# P_08__CPU_MISC.net
KiCad netlist of a schematic drawn in Altium Designer
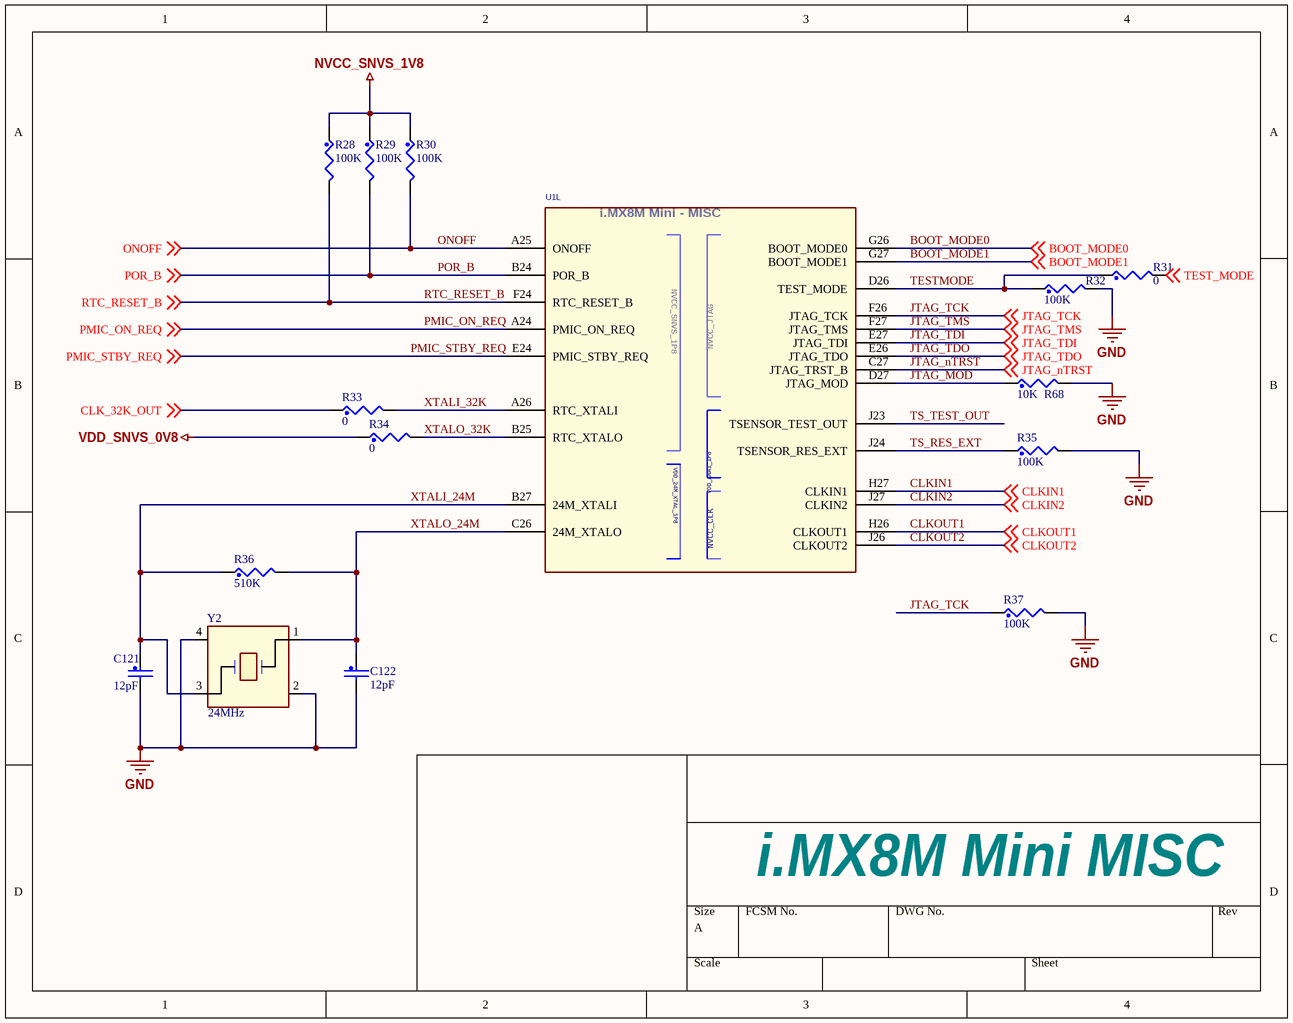
[diagram p0: P[08]_CPU_MISC.SchDoc]

(export (version "E")
  (design (tool "Eeschema 10.0.6"))
  (components
    (comp (ref "C121")
      (value "12pF")
      (footprint "0201_CC - C")
      (libsource (lib "AA_iMX8_M_") (part "CAP_NP"))
    )
    (comp (ref "C122")
      (value "12pF")
      (footprint "0201_CC - C")
      (libsource (lib "AA_iMX8_M_") (part "CAP_NP"))
    )
    (comp (ref "R28") (value "100K") (footprint "0201_CC") (libsource (lib "AA_iMX8_M_") (part "RES")))
    (comp (ref "R29") (value "100K") (footprint "0201_CC") (libsource (lib "AA_iMX8_M_") (part "RES")))
    (comp (ref "R30") (value "100K") (footprint "0201_CC") (libsource (lib "AA_iMX8_M_") (part "RES")))
    (comp (ref "R31") (value "0") (footprint "0402_CC") (libsource (lib "AA_iMX8_M_") (part "RES")))
    (comp (ref "R32") (value "100K") (footprint "0201_CC") (libsource (lib "AA_iMX8_M_") (part "RES")))
    (comp (ref "R33") (value "0") (footprint "0402_CC") (libsource (lib "AA_iMX8_M_") (part "RES")))
    (comp (ref "R34") (value "0") (footprint "0402_CC") (libsource (lib "AA_iMX8_M_") (part "RES")))
    (comp (ref "R35") (value "100K") (footprint "0201_CC") (libsource (lib "AA_iMX8_M_") (part "RES")))
    (comp (ref "R36") (value "510K") (footprint "0402_CC") (libsource (lib "AA_iMX8_M_") (part "RES")))
    (comp (ref "R37") (value "100K") (footprint "0201_CC") (libsource (lib "AA_iMX8_M_") (part "RES")))
    (comp (ref "R68") (value "10K") (footprint "0201_CC") (libsource (lib "AA_iMX8_M_") (part "RES")))
    (comp (ref "U1")
      (value "SFP_CGND")
      (footprint "BGA486_0P5_14X14")
      (description "IC CPU QUAD CORTEX A53+M4 1.8GHZ BGA486 / By Arman Arvand")
      (libsource (lib "AA_iMX8_M_") (part "MIMX8MM_BGA486P"))
    )
    (comp (ref "Y2")
      (value "24MHz")
      (footprint "OSCCC320X250X60")
      (libsource (lib "AA_iMX8_M_") (part "XTAL_13Y"))
    )
  )
  (nets
    (net (code "1") (name "/JTAG_MOD") (class "Default")
      (node (ref "R68") (pin "1") (pinfunction "1_1") (pintype "passive"))
      (node (ref "U1") (pin "D27") (pinfunction "JTAG_MOD_D27") (pintype "passive"))
    )
    (net (code "2") (name "/TESTMODE") (class "Default")
      (node (ref "R31") (pin "1") (pinfunction "1_1") (pintype "passive"))
      (node (ref "R32") (pin "1") (pinfunction "1_1") (pintype "passive"))
      (node (ref "U1") (pin "D26") (pinfunction "TEST_MODE_D26") (pintype "passive"))
    )
    (net (code "3") (name "/TS_RES_EXT") (class "Default")
      (node (ref "R35") (pin "1") (pinfunction "1_1") (pintype "passive"))
      (node (ref "U1") (pin "J24") (pinfunction "TSENSOR_RES_EXT_J24") (pintype "passive"))
    )
    (net (code "4") (name "/TS_TEST_OUT") (class "Default")
      (node (ref "U1") (pin "J23") (pinfunction "TSENSOR_TEST_OUT_J23") (pintype "passive"))
    )
    (net (code "5") (name "/XTALI_24M") (class "Default")
      (node (ref "C121") (pin "1") (pinfunction "1_1") (pintype "passive"))
      (node (ref "R36") (pin "1") (pinfunction "1_1") (pintype "passive"))
      (node (ref "U1") (pin "B27") (pinfunction "24M_XTALI_B27") (pintype "passive"))
      (node (ref "Y2") (pin "3") (pinfunction "3_3") (pintype "passive"))
    )
    (net (code "6") (name "/XTALI_32K") (class "Default")
      (node (ref "R33") (pin "2") (pinfunction "2_2") (pintype "passive"))
      (node (ref "U1") (pin "A26") (pinfunction "RTC_XTALI_A26") (pintype "passive"))
    )
    (net (code "7") (name "/XTALO_24M") (class "Default")
      (node (ref "C122") (pin "1") (pinfunction "1_1") (pintype "passive"))
      (node (ref "R36") (pin "2") (pinfunction "2_2") (pintype "passive"))
      (node (ref "U1") (pin "C26") (pinfunction "24M_XTALO_C26") (pintype "passive"))
      (node (ref "Y2") (pin "1") (pinfunction "1_1") (pintype "passive"))
    )
    (net (code "8") (name "/XTALO_32K") (class "Default")
      (node (ref "R34") (pin "2") (pinfunction "2_2") (pintype "passive"))
      (node (ref "U1") (pin "B25") (pinfunction "RTC_XTALO_B25") (pintype "passive"))
    )
    (net (code "9") (name "BOOT_MODE0") (class "Default")
      (node (ref "U1") (pin "G26") (pinfunction "BOOT_MODE0_G26") (pintype "passive"))
    )
    (net (code "10") (name "BOOT_MODE1") (class "Default")
      (node (ref "U1") (pin "G27") (pinfunction "BOOT_MODE1_G27") (pintype "passive"))
    )
    (net (code "11") (name "CLKIN1") (class "Default")
      (node (ref "U1") (pin "H27") (pinfunction "CLKIN1_H27") (pintype "passive"))
    )
    (net (code "12") (name "CLKIN2") (class "Default")
      (node (ref "U1") (pin "J27") (pinfunction "CLKIN2_J27") (pintype "passive"))
    )
    (net (code "13") (name "CLKOUT1") (class "Default")
      (node (ref "U1") (pin "H26") (pinfunction "CLKOUT1_H26") (pintype "passive"))
    )
    (net (code "14") (name "CLKOUT2") (class "Default")
      (node (ref "U1") (pin "J26") (pinfunction "CLKOUT2_J26") (pintype "passive"))
    )
    (net (code "15") (name "CLK_32K_OUT") (class "Default")
      (node (ref "R33") (pin "1") (pinfunction "1_1") (pintype "passive"))
    )
    (net (code "16") (name "GND") (class "Default")
      (node (ref "C121") (pin "2") (pinfunction "2_2") (pintype "passive"))
      (node (ref "C122") (pin "2") (pinfunction "2_2") (pintype "passive"))
      (node (ref "R32") (pin "2") (pinfunction "2_2") (pintype "passive"))
      (node (ref "R35") (pin "2") (pinfunction "2_2") (pintype "passive"))
      (node (ref "R37") (pin "2") (pinfunction "2_2") (pintype "passive"))
      (node (ref "R68") (pin "2") (pinfunction "2_2") (pintype "passive"))
      (node (ref "Y2") (pin "2") (pinfunction "2_2") (pintype "passive"))
      (node (ref "Y2") (pin "4") (pinfunction "4_4") (pintype "passive"))
    )
    (net (code "17") (name "JTAG_TCK") (class "Default")
      (node (ref "R37") (pin "1") (pinfunction "1_1") (pintype "passive"))
      (node (ref "U1") (pin "F26") (pinfunction "JTAG_TCK_F26") (pintype "passive"))
    )
    (net (code "18") (name "JTAG_TDI") (class "Default")
      (node (ref "U1") (pin "E27") (pinfunction "JTAG_TDI_E27") (pintype "passive"))
    )
    (net (code "19") (name "JTAG_TDO") (class "Default")
      (node (ref "U1") (pin "E26") (pinfunction "JTAG_TDO_E26") (pintype "passive"))
    )
    (net (code "20") (name "JTAG_TMS") (class "Default")
      (node (ref "U1") (pin "F27") (pinfunction "JTAG_TMS_F27") (pintype "passive"))
    )
    (net (code "21") (name "JTAG_nTRST") (class "Default")
      (node (ref "U1") (pin "C27") (pinfunction "JTAG_TRST_B_C27") (pintype "passive"))
    )
    (net (code "22") (name "NVCC_SNVS_1V8") (class "Default")
      (node (ref "R28") (pin "1") (pinfunction "1_1") (pintype "passive"))
      (node (ref "R29") (pin "1") (pinfunction "1_1") (pintype "passive"))
      (node (ref "R30") (pin "1") (pinfunction "1_1") (pintype "passive"))
    )
    (net (code "23") (name "ONOFF") (class "Default")
      (node (ref "R30") (pin "2") (pinfunction "2_2") (pintype "passive"))
      (node (ref "U1") (pin "A25") (pinfunction "ONOFF_A25") (pintype "passive"))
    )
    (net (code "24") (name "PMIC_ON_REQ") (class "Default")
      (node (ref "U1") (pin "A24") (pinfunction "PMIC_ON_REQ_A24") (pintype "passive"))
    )
    (net (code "25") (name "PMIC_STBY_REQ") (class "Default")
      (node (ref "U1") (pin "E24") (pinfunction "PMIC_STBY_REQ_E24") (pintype "passive"))
    )
    (net (code "26") (name "POR_B") (class "Default")
      (node (ref "R29") (pin "2") (pinfunction "2_2") (pintype "passive"))
      (node (ref "U1") (pin "B24") (pinfunction "POR_B_B24") (pintype "passive"))
    )
    (net (code "27") (name "RTC_RESET_B") (class "Default")
      (node (ref "R28") (pin "2") (pinfunction "2_2") (pintype "passive"))
      (node (ref "U1") (pin "F24") (pinfunction "RTC_RESET_B_F24") (pintype "passive"))
    )
    (net (code "28") (name "TEST_MODE") (class "Default")
      (node (ref "R31") (pin "2") (pinfunction "2_2") (pintype "passive"))
    )
    (net (code "29") (name "VDD_SNVS_0V8") (class "Default")
      (node (ref "R34") (pin "1") (pinfunction "1_1") (pintype "passive"))
    )
  )
)
